# CPU-SOLDER_V2.net
KiCad netlist of a schematic drawn in EAGLE
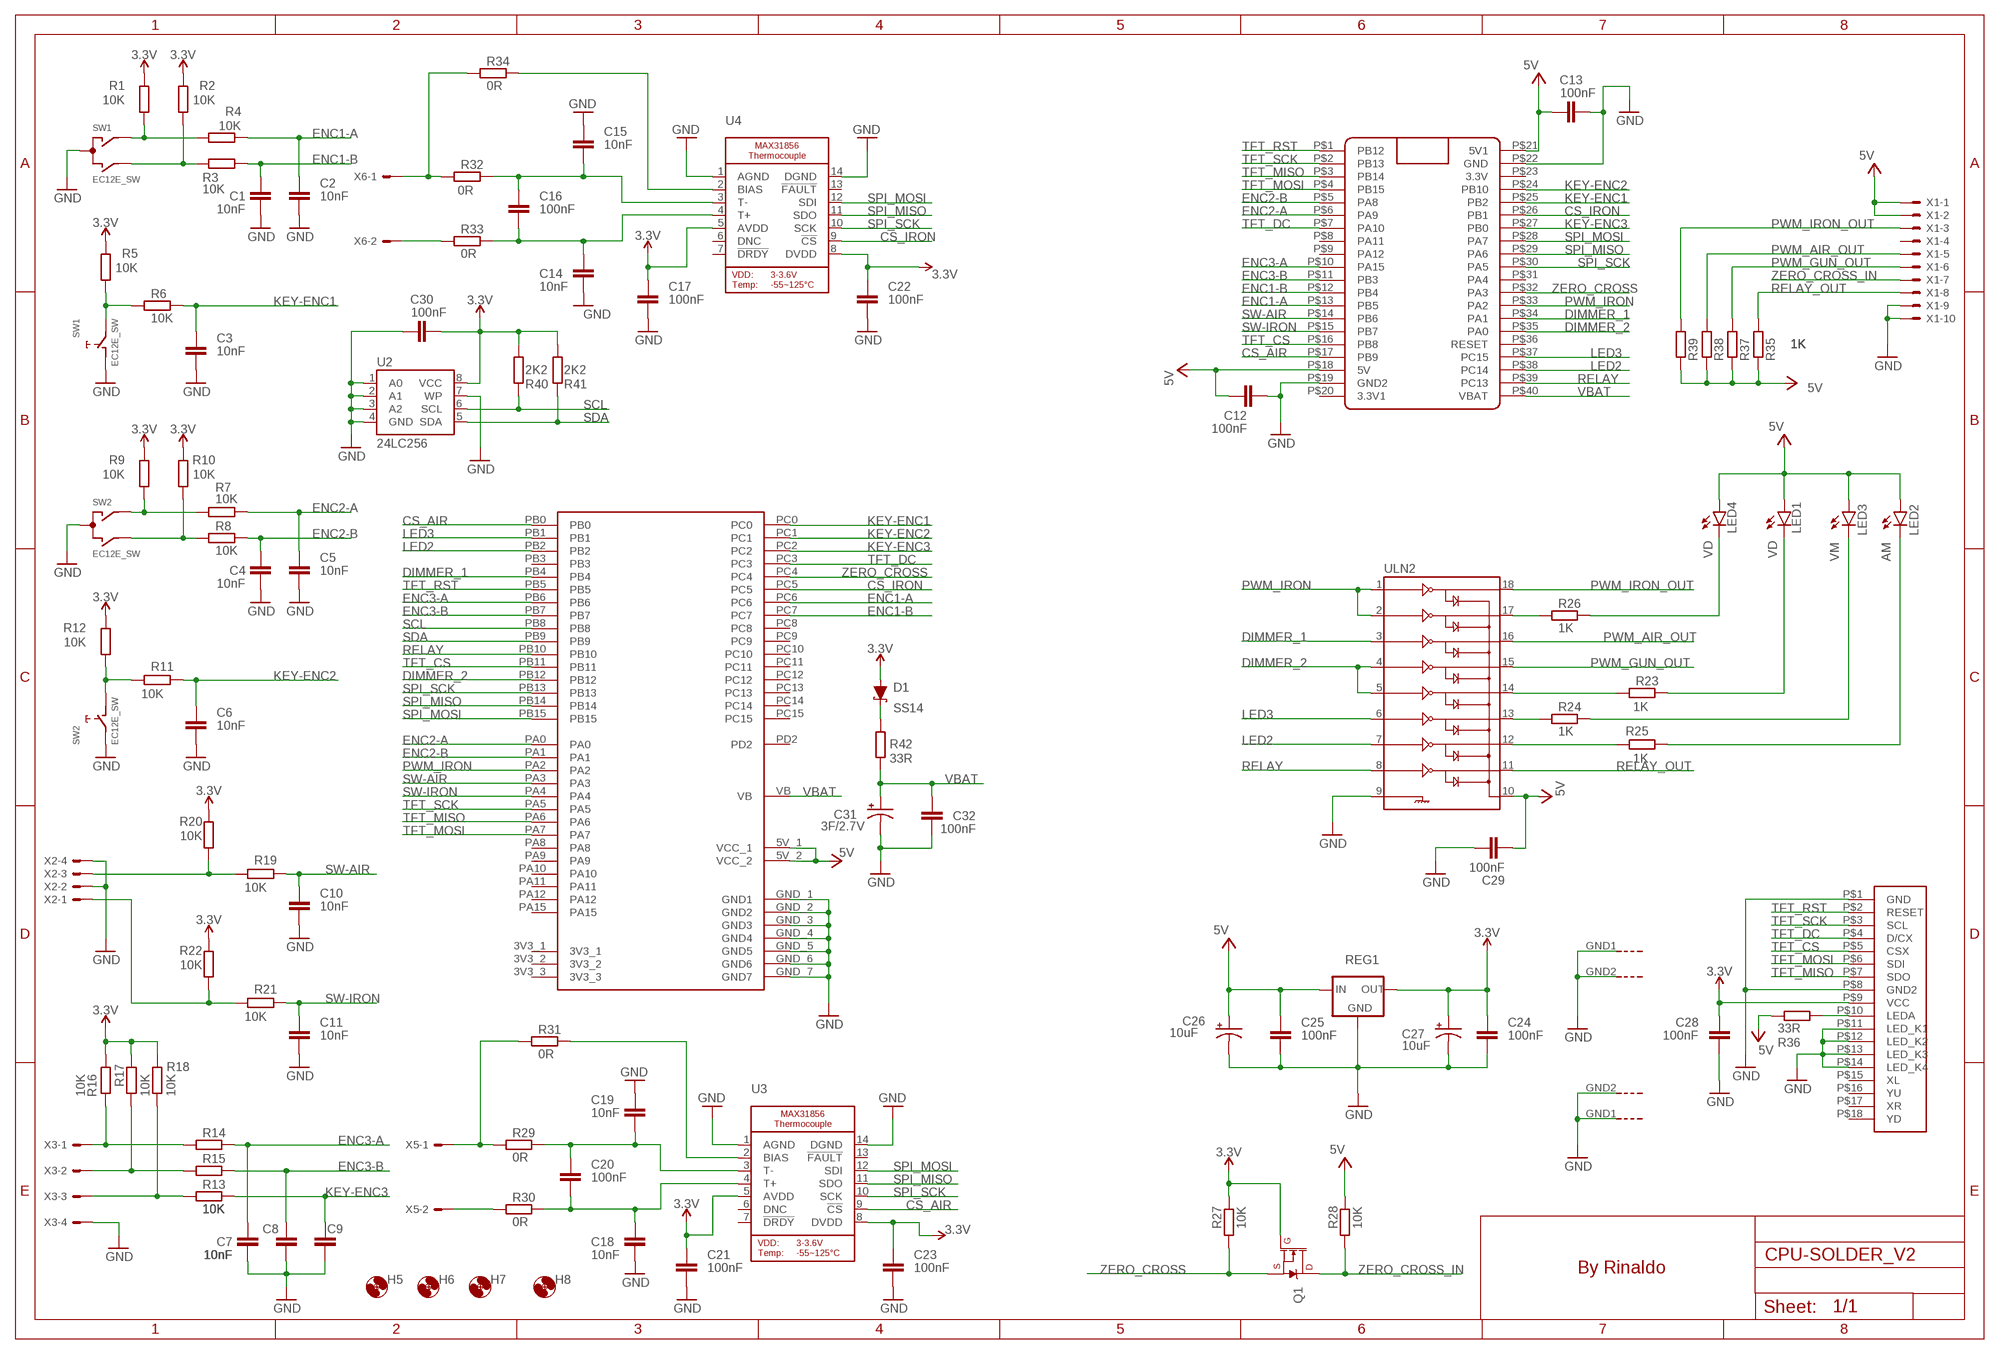
[diagram p0: schematic, sheet 1]

(export (version "E")
  (design (tool "Eeschema 10.0.6"))
  (components
    (comp (ref "C1")
      (value "10nF")
      (footprint "eagle-import:C0603")
      (libsource (lib "eagle-import") (part "C-EUC0603"))
    )
    (comp (ref "C2")
      (value "10nF")
      (footprint "eagle-import:C0603")
      (libsource (lib "eagle-import") (part "C-EUC0603"))
    )
    (comp (ref "C3")
      (value "10nF")
      (footprint "eagle-import:C0603")
      (libsource (lib "eagle-import") (part "C-EUC0603"))
    )
    (comp (ref "C4")
      (value "10nF")
      (footprint "eagle-import:C0603")
      (libsource (lib "eagle-import") (part "C-EUC0603"))
    )
    (comp (ref "C5")
      (value "10nF")
      (footprint "eagle-import:C0603")
      (libsource (lib "eagle-import") (part "C-EUC0603"))
    )
    (comp (ref "C6")
      (value "10nF")
      (footprint "eagle-import:C0603")
      (libsource (lib "eagle-import") (part "C-EUC0603"))
    )
    (comp (ref "C7")
      (value "10nF")
      (footprint "eagle-import:C0603")
      (libsource (lib "eagle-import") (part "C-EUC0603"))
    )
    (comp (ref "C8")
      (value "10nF")
      (footprint "eagle-import:C0603")
      (libsource (lib "eagle-import") (part "C-EUC0603"))
    )
    (comp (ref "C9")
      (value "10nF")
      (footprint "eagle-import:C0603")
      (libsource (lib "eagle-import") (part "C-EUC0603"))
    )
    (comp (ref "C10")
      (value "10nF")
      (footprint "eagle-import:C0603")
      (libsource (lib "eagle-import") (part "C-EUC0603"))
    )
    (comp (ref "C11")
      (value "10nF")
      (footprint "eagle-import:C0603")
      (libsource (lib "eagle-import") (part "C-EUC0603"))
    )
    (comp (ref "C12")
      (value "100nF")
      (footprint "eagle-import:C0603")
      (libsource (lib "eagle-import") (part "C-EUC0603"))
    )
    (comp (ref "C13")
      (value "100nF")
      (footprint "eagle-import:C0603")
      (libsource (lib "eagle-import") (part "C-EUC0603"))
    )
    (comp (ref "C14")
      (value "10nF")
      (footprint "eagle-import:C0603")
      (libsource (lib "eagle-import") (part "C-EUC0603"))
    )
    (comp (ref "C15")
      (value "10nF")
      (footprint "eagle-import:C0603")
      (libsource (lib "eagle-import") (part "C-EUC0603"))
    )
    (comp (ref "C16")
      (value "100nF")
      (footprint "eagle-import:C0603")
      (libsource (lib "eagle-import") (part "C-EUC0603"))
    )
    (comp (ref "C17")
      (value "100nF")
      (footprint "eagle-import:C0603")
      (libsource (lib "eagle-import") (part "C-EUC0603"))
    )
    (comp (ref "C18")
      (value "10nF")
      (footprint "eagle-import:C0603")
      (libsource (lib "eagle-import") (part "C-EUC0603"))
    )
    (comp (ref "C19")
      (value "10nF")
      (footprint "eagle-import:C0603")
      (libsource (lib "eagle-import") (part "C-EUC0603"))
    )
    (comp (ref "C20")
      (value "100nF")
      (footprint "eagle-import:C0603")
      (libsource (lib "eagle-import") (part "C-EUC0603"))
    )
    (comp (ref "C21")
      (value "100nF")
      (footprint "eagle-import:C0603")
      (libsource (lib "eagle-import") (part "C-EUC0603"))
    )
    (comp (ref "C22")
      (value "100nF")
      (footprint "eagle-import:C0603")
      (libsource (lib "eagle-import") (part "C-EUC0603"))
    )
    (comp (ref "C23")
      (value "100nF")
      (footprint "eagle-import:C0603")
      (libsource (lib "eagle-import") (part "C-EUC0603"))
    )
    (comp (ref "C24")
      (value "100nF")
      (footprint "eagle-import:C0603")
      (libsource (lib "eagle-import") (part "C-EUC0603"))
    )
    (comp (ref "C25")
      (value "100nF")
      (footprint "eagle-import:C0603")
      (libsource (lib "eagle-import") (part "C-EUC0603"))
    )
    (comp (ref "C26")
      (value "10uF")
      (footprint "eagle-import:EIA3528")
      (libsource (lib "eagle-import") (part "10UF-POLAR-EIA3528-20V-10%(TANT)"))
    )
    (comp (ref "C27")
      (value "10uF")
      (footprint "eagle-import:EIA3528")
      (libsource (lib "eagle-import") (part "10UF-POLAR-EIA3528-20V-10%(TANT)"))
    )
    (comp (ref "C28")
      (value "100nF")
      (footprint "eagle-import:C0603")
      (libsource (lib "eagle-import") (part "C-EUC0603"))
    )
    (comp (ref "C29")
      (value "100nF")
      (footprint "eagle-import:C0603")
      (libsource (lib "eagle-import") (part "C-EUC0603"))
    )
    (comp (ref "C30")
      (value "100nF")
      (footprint "eagle-import:C0603")
      (libsource (lib "eagle-import") (part "C-EUC0603"))
    )
    (comp (ref "C31")
      (value "3F/2.7V")
      (footprint "eagle-import:CPOL-RADIAL-1F-2.7V")
      (libsource (lib "eagle-import") (part "1F-2.7V(PTH)CPOL-RADIAL-1H-2.7V"))
    )
    (comp (ref "C32")
      (value "100nF")
      (footprint "eagle-import:C0603")
      (libsource (lib "eagle-import") (part "C-EUC0603"))
    )
    (comp (ref "D1")
      (value "SS14")
      (footprint "eagle-import:SMA-DIODE")
      (libsource (lib "eagle-import") (part "DIODE-SCHOTTKY-SS14"))
    )
    (comp (ref "H5")
      (value "MOUNT-HOLE3.6")
      (footprint "eagle-import:3,6")
      (libsource (lib "eagle-import") (part "MOUNT-HOLE3.6"))
    )
    (comp (ref "H6")
      (value "MOUNT-HOLE3.6")
      (footprint "eagle-import:3,6")
      (libsource (lib "eagle-import") (part "MOUNT-HOLE3.6"))
    )
    (comp (ref "H7")
      (value "MOUNT-HOLE3.6")
      (footprint "eagle-import:3,6")
      (libsource (lib "eagle-import") (part "MOUNT-HOLE3.6"))
    )
    (comp (ref "H8")
      (value "MOUNT-HOLE3.6")
      (footprint "eagle-import:3,6")
      (libsource (lib "eagle-import") (part "MOUNT-HOLE3.6"))
    )
    (comp (ref "LCD1")
      (value "ILI9341-3.2")
      (footprint "eagle-import:ILI9341-3.2")
      (libsource (lib "eagle-import") (part "ILI9341-3.2"))
    )
    (comp (ref "LED1")
      (value "VD")
      (footprint "eagle-import:LED5MM")
      (libsource (lib "eagle-import") (part "LED5MM"))
    )
    (comp (ref "LED2")
      (value "AM")
      (footprint "eagle-import:LED5MM")
      (libsource (lib "eagle-import") (part "LED5MM"))
    )
    (comp (ref "LED3")
      (value "VM")
      (footprint "eagle-import:LED5MM")
      (libsource (lib "eagle-import") (part "LED5MM"))
    )
    (comp (ref "LED4")
      (value "VD")
      (footprint "eagle-import:LED5MM")
      (libsource (lib "eagle-import") (part "LED5MM"))
    )
    (comp (ref "Q1")
      (value "220mA/50V/3.5Ω")
      (footprint "eagle-import:SOT23-3")
      (libsource (lib "eagle-import") (part "MOSFET-NCH-BSS138"))
    )
    (comp (ref "R1")
      (value "10K")
      (footprint "eagle-import:R0603")
      (libsource (lib "eagle-import") (part "R-EU_R0603"))
    )
    (comp (ref "R2")
      (value "10K")
      (footprint "eagle-import:R0603")
      (libsource (lib "eagle-import") (part "R-EU_R0603"))
    )
    (comp (ref "R3")
      (value "10K")
      (footprint "eagle-import:R0603")
      (libsource (lib "eagle-import") (part "R-EU_R0603"))
    )
    (comp (ref "R4")
      (value "10K")
      (footprint "eagle-import:R0603")
      (libsource (lib "eagle-import") (part "R-EU_R0603"))
    )
    (comp (ref "R5")
      (value "10K")
      (footprint "eagle-import:R0603")
      (libsource (lib "eagle-import") (part "R-EU_R0603"))
    )
    (comp (ref "R6")
      (value "10K")
      (footprint "eagle-import:R0603")
      (libsource (lib "eagle-import") (part "R-EU_R0603"))
    )
    (comp (ref "R7")
      (value "10K")
      (footprint "eagle-import:R0603")
      (libsource (lib "eagle-import") (part "R-EU_R0603"))
    )
    (comp (ref "R8")
      (value "10K")
      (footprint "eagle-import:R0603")
      (libsource (lib "eagle-import") (part "R-EU_R0603"))
    )
    (comp (ref "R9")
      (value "10K")
      (footprint "eagle-import:R0603")
      (libsource (lib "eagle-import") (part "R-EU_R0603"))
    )
    (comp (ref "R10")
      (value "10K")
      (footprint "eagle-import:R0603")
      (libsource (lib "eagle-import") (part "R-EU_R0603"))
    )
    (comp (ref "R11")
      (value "10K")
      (footprint "eagle-import:R0603")
      (libsource (lib "eagle-import") (part "R-EU_R0603"))
    )
    (comp (ref "R12")
      (value "10K")
      (footprint "eagle-import:R0603")
      (libsource (lib "eagle-import") (part "R-EU_R0603"))
    )
    (comp (ref "R13")
      (value "10K")
      (footprint "eagle-import:R0603")
      (libsource (lib "eagle-import") (part "R-EU_R0603"))
    )
    (comp (ref "R14")
      (value "10K")
      (footprint "eagle-import:R0603")
      (libsource (lib "eagle-import") (part "R-EU_R0603"))
    )
    (comp (ref "R15")
      (value "10K")
      (footprint "eagle-import:R0603")
      (libsource (lib "eagle-import") (part "R-EU_R0603"))
    )
    (comp (ref "R16")
      (value "10K")
      (footprint "eagle-import:R0603")
      (libsource (lib "eagle-import") (part "R-EU_R0603"))
    )
    (comp (ref "R17")
      (value "10K")
      (footprint "eagle-import:R0603")
      (libsource (lib "eagle-import") (part "R-EU_R0603"))
    )
    (comp (ref "R18")
      (value "10K")
      (footprint "eagle-import:R0603")
      (libsource (lib "eagle-import") (part "R-EU_R0603"))
    )
    (comp (ref "R19")
      (value "10K")
      (footprint "eagle-import:R0603")
      (libsource (lib "eagle-import") (part "R-EU_R0603"))
    )
    (comp (ref "R20")
      (value "10K")
      (footprint "eagle-import:R0603")
      (libsource (lib "eagle-import") (part "R-EU_R0603"))
    )
    (comp (ref "R21")
      (value "10K")
      (footprint "eagle-import:R0603")
      (libsource (lib "eagle-import") (part "R-EU_R0603"))
    )
    (comp (ref "R22")
      (value "10K")
      (footprint "eagle-import:R0603")
      (libsource (lib "eagle-import") (part "R-EU_R0603"))
    )
    (comp (ref "R23")
      (value "1K")
      (footprint "eagle-import:R0603")
      (libsource (lib "eagle-import") (part "R-EU_R0603"))
    )
    (comp (ref "R24")
      (value "1K")
      (footprint "eagle-import:R0603")
      (libsource (lib "eagle-import") (part "R-EU_R0603"))
    )
    (comp (ref "R25")
      (value "1K")
      (footprint "eagle-import:R0603")
      (libsource (lib "eagle-import") (part "R-EU_R0603"))
    )
    (comp (ref "R26")
      (value "1K")
      (footprint "eagle-import:R0603")
      (libsource (lib "eagle-import") (part "R-EU_R0603"))
    )
    (comp (ref "R27")
      (value "10K")
      (footprint "eagle-import:R0603")
      (libsource (lib "eagle-import") (part "R-EU_R0603"))
    )
    (comp (ref "R28")
      (value "10K")
      (footprint "eagle-import:R0603")
      (libsource (lib "eagle-import") (part "R-EU_R0603"))
    )
    (comp (ref "R29")
      (value "0R")
      (footprint "eagle-import:R0603")
      (libsource (lib "eagle-import") (part "R-EU_R0603"))
    )
    (comp (ref "R30")
      (value "0R")
      (footprint "eagle-import:R0603")
      (libsource (lib "eagle-import") (part "R-EU_R0603"))
    )
    (comp (ref "R31")
      (value "0R")
      (footprint "eagle-import:R0603")
      (libsource (lib "eagle-import") (part "R-EU_R0603"))
    )
    (comp (ref "R32")
      (value "0R")
      (footprint "eagle-import:R0603")
      (libsource (lib "eagle-import") (part "R-EU_R0603"))
    )
    (comp (ref "R33")
      (value "0R")
      (footprint "eagle-import:R0603")
      (libsource (lib "eagle-import") (part "R-EU_R0603"))
    )
    (comp (ref "R34")
      (value "0R")
      (footprint "eagle-import:R0603")
      (libsource (lib "eagle-import") (part "R-EU_R0603"))
    )
    (comp (ref "R35")
      (value "1K")
      (footprint "eagle-import:R0603")
      (libsource (lib "eagle-import") (part "R-EU_R0603"))
    )
    (comp (ref "R36")
      (value "33R")
      (footprint "eagle-import:R2512")
      (libsource (lib "eagle-import") (part "R-EU_R2512"))
    )
    (comp (ref "R37")
      (value "1K")
      (footprint "eagle-import:R0603")
      (libsource (lib "eagle-import") (part "R-EU_R0603"))
    )
    (comp (ref "R38")
      (value "1K")
      (footprint "eagle-import:R0603")
      (libsource (lib "eagle-import") (part "R-EU_R0603"))
    )
    (comp (ref "R39")
      (value "1K")
      (footprint "eagle-import:R0603")
      (libsource (lib "eagle-import") (part "R-EU_R0603"))
    )
    (comp (ref "R40")
      (value "2K2")
      (footprint "eagle-import:R0603")
      (libsource (lib "eagle-import") (part "R-EU_R0603"))
    )
    (comp (ref "R41")
      (value "2K2")
      (footprint "eagle-import:R0603")
      (libsource (lib "eagle-import") (part "R-EU_R0603"))
    )
    (comp (ref "R42")
      (value "33R")
      (footprint "eagle-import:R2512")
      (libsource (lib "eagle-import") (part "R-EU_R2512"))
    )
    (comp (ref "REG1")
      (value "V_REG_LD1117VXXLD1117-SMD")
      (footprint "eagle-import:SOT223")
      (libsource (lib "eagle-import") (part "V_REG_LD1117VXXLD1117-SMD"))
    )
    (comp (ref "SW1")
      (value "EC12E_SW")
      (footprint "eagle-import:ALPS_EC12E_SW")
      (fields (field (name "MPN") "EC12E2424407"))
      (libsource (lib "eagle-import") (part "EC12E_SW"))
    )
    (comp (ref "SW2")
      (value "EC12E_SW")
      (footprint "eagle-import:ALPS_EC12E_SW")
      (fields (field (name "MPN") "EC12E2424407"))
      (libsource (lib "eagle-import") (part "EC12E_SW"))
    )
    (comp (ref "U1")
      (value "STM32-F411")
      (footprint "eagle-import:BLACK-PILL-STM32_BLUE_PILL")
      (libsource (lib "eagle-import") (part "BLACK-PILL-STM32_BLACK_PILL"))
    )
    (comp (ref "U2")
      (value "24LC256")
      (footprint "eagle-import:SO08")
      (libsource (lib "eagle-import") (part "EEPROM-I2C256K"))
    )
    (comp (ref "U3")
      (value "MICROBUILDER_MAX31856")
      (footprint "eagle-import:MICROBUILDER_TSSOP14")
      (libsource (lib "eagle-import") (part "MICROBUILDER_MAX31856"))
    )
    (comp (ref "U4")
      (value "MICROBUILDER_MAX31856")
      (footprint "eagle-import:MICROBUILDER_TSSOP14")
      (libsource (lib "eagle-import") (part "MICROBUILDER_MAX31856"))
    )
    (comp (ref "U5")
      (value "F405_WEACT")
      (footprint "eagle-import:F405_WEACT")
      (libsource (lib "eagle-import") (part "F405_WEACT"))
    )
    (comp (ref "ULN2")
      (value "ULN2803SOICW")
      (footprint "eagle-import:SO18L")
      (libsource (lib "eagle-import") (part "ULN2803SOICW"))
    )
    (comp (ref "X1")
      (value "JST-XH-10-PIN-ROUND-PAD")
      (footprint "eagle-import:JST-XH-10-PACKAGE-ROUND-PAD")
      (libsource (lib "eagle-import") (part "JST-XH-10-PIN-ROUND-PAD"))
    )
    (comp (ref "X2")
      (value "JST-XH-04-PIN-ROUND-PAD")
      (footprint "eagle-import:JST-XH-04-PACKAGE-ROUND-PAD")
      (libsource (lib "eagle-import") (part "JST-XH-04-PIN-ROUND-PAD"))
    )
    (comp (ref "X3")
      (value "JST-XH-04-PIN-ROUND-PAD")
      (footprint "eagle-import:JST-XH-04-PACKAGE-ROUND-PAD")
      (libsource (lib "eagle-import") (part "JST-XH-04-PIN-ROUND-PAD"))
    )
    (comp (ref "X5")
      (value "JST-XH-02-PIN-ROUND-PAD")
      (footprint "eagle-import:JST-XH-02-PACKAGE-ROUND-PAD")
      (libsource (lib "eagle-import") (part "JST-XH-02-PIN-ROUND-PAD"))
    )
    (comp (ref "X6")
      (value "JST-XH-02-PIN-ROUND-PAD")
      (footprint "eagle-import:JST-XH-02-PACKAGE-ROUND-PAD")
      (libsource (lib "eagle-import") (part "JST-XH-02-PIN-ROUND-PAD"))
    )
  )
  (nets
    (net (code "1") (name "/CS_AIR") (class "Default")
      (node (ref "U1") (pin "P$17") (pinfunction "PB9_P$17") (pintype "bidirectional"))
      (node (ref "U3") (pin "9") (pinfunction "~{CS}_9") (pintype "input"))
      (node (ref "U5") (pin "PB0") (pinfunction "PB0_PB0") (pintype "bidirectional"))
    )
    (net (code "2") (name "/CS_IRON") (class "Default")
      (node (ref "U1") (pin "P$26") (pinfunction "PB1_P$26") (pintype "bidirectional"))
      (node (ref "U4") (pin "9") (pinfunction "~{CS}_9") (pintype "input"))
      (node (ref "U5") (pin "PC5") (pinfunction "PC5_PC5") (pintype "bidirectional"))
    )
    (net (code "3") (name "/DIMMER_1") (class "Default")
      (node (ref "U1") (pin "P$34") (pinfunction "PA1_P$34") (pintype "bidirectional"))
      (node (ref "U5") (pin "PB4") (pinfunction "PB4_PB4") (pintype "bidirectional"))
      (node (ref "ULN2") (pin "3") (pinfunction "3_3") (pintype "bidirectional"))
    )
    (net (code "4") (name "/DIMMER_2") (class "Default")
      (node (ref "U1") (pin "P$35") (pinfunction "PA0_P$35") (pintype "bidirectional"))
      (node (ref "U5") (pin "PB12") (pinfunction "PB12_PB12") (pintype "bidirectional"))
      (node (ref "ULN2") (pin "4") (pinfunction "4_4") (pintype "bidirectional"))
      (node (ref "ULN2") (pin "5") (pinfunction "5_5") (pintype "bidirectional"))
    )
    (net (code "5") (name "/ENC1-A") (class "Default")
      (node (ref "C2") (pin "1") (pinfunction "1_1") (pintype "passive"))
      (node (ref "R3") (pin "1") (pinfunction "1_1") (pintype "passive"))
      (node (ref "U1") (pin "P$13") (pinfunction "PB5_P$13") (pintype "bidirectional"))
      (node (ref "U5") (pin "PC6") (pinfunction "PC6_PC6") (pintype "bidirectional"))
    )
    (net (code "6") (name "/ENC1-B") (class "Default")
      (node (ref "C1") (pin "1") (pinfunction "1_1") (pintype "passive"))
      (node (ref "R4") (pin "2") (pinfunction "2_2") (pintype "passive"))
      (node (ref "U1") (pin "P$12") (pinfunction "PB4_P$12") (pintype "bidirectional"))
      (node (ref "U5") (pin "PC7") (pinfunction "PC7_PC7") (pintype "bidirectional"))
    )
    (net (code "7") (name "/ENC2-A") (class "Default")
      (node (ref "C5") (pin "1") (pinfunction "1_1") (pintype "passive"))
      (node (ref "R7") (pin "2") (pinfunction "2_2") (pintype "passive"))
      (node (ref "U1") (pin "P$6") (pinfunction "PA9_P$6") (pintype "bidirectional"))
      (node (ref "U5") (pin "PA0") (pinfunction "PA0_PA0") (pintype "bidirectional"))
    )
    (net (code "8") (name "/ENC2-B") (class "Default")
      (node (ref "C4") (pin "1") (pinfunction "1_1") (pintype "passive"))
      (node (ref "R8") (pin "2") (pinfunction "2_2") (pintype "passive"))
      (node (ref "U1") (pin "P$5") (pinfunction "PA8_P$5") (pintype "bidirectional"))
      (node (ref "U5") (pin "PA1") (pinfunction "PA1_PA1") (pintype "bidirectional"))
    )
    (net (code "9") (name "/ENC3-A") (class "Default")
      (node (ref "C7") (pin "1") (pinfunction "1_1") (pintype "passive"))
      (node (ref "R14") (pin "2") (pinfunction "2_2") (pintype "passive"))
      (node (ref "U1") (pin "P$10") (pinfunction "PA15_P$10") (pintype "bidirectional"))
      (node (ref "U5") (pin "PB6") (pinfunction "PB6_PB6") (pintype "bidirectional"))
    )
    (net (code "10") (name "/ENC3-B") (class "Default")
      (node (ref "C8") (pin "1") (pinfunction "1_1") (pintype "passive"))
      (node (ref "R15") (pin "2") (pinfunction "2_2") (pintype "passive"))
      (node (ref "U1") (pin "P$11") (pinfunction "PB3_P$11") (pintype "bidirectional"))
      (node (ref "U5") (pin "PB7") (pinfunction "PB7_PB7") (pintype "bidirectional"))
    )
    (net (code "11") (name "/KEY-ENC1") (class "Default")
      (node (ref "C3") (pin "1") (pinfunction "1_1") (pintype "passive"))
      (node (ref "R6") (pin "1") (pinfunction "1_1") (pintype "passive"))
      (node (ref "U1") (pin "P$25") (pinfunction "PB2_P$25") (pintype "bidirectional"))
      (node (ref "U5") (pin "PC0") (pinfunction "PC0_PC0") (pintype "bidirectional"))
    )
    (net (code "12") (name "/KEY-ENC2") (class "Default")
      (node (ref "C6") (pin "1") (pinfunction "1_1") (pintype "passive"))
      (node (ref "R11") (pin "1") (pinfunction "1_1") (pintype "passive"))
      (node (ref "U1") (pin "P$24") (pinfunction "PB10_P$24") (pintype "bidirectional"))
      (node (ref "U5") (pin "PC1") (pinfunction "PC1_PC1") (pintype "bidirectional"))
    )
    (net (code "13") (name "/KEY-ENC3") (class "Default")
      (node (ref "C9") (pin "1") (pinfunction "1_1") (pintype "passive"))
      (node (ref "R13") (pin "2") (pinfunction "2_2") (pintype "passive"))
      (node (ref "U1") (pin "P$27") (pinfunction "PB0_P$27") (pintype "bidirectional"))
      (node (ref "U5") (pin "PC2") (pinfunction "PC2_PC2") (pintype "bidirectional"))
    )
    (net (code "14") (name "/LED2") (class "Default")
      (node (ref "U1") (pin "P$38") (pinfunction "PC14_P$38") (pintype "bidirectional"))
      (node (ref "U5") (pin "PB2") (pinfunction "PB2_PB2") (pintype "bidirectional"))
      (node (ref "ULN2") (pin "7") (pinfunction "7_7") (pintype "bidirectional"))
    )
    (net (code "15") (name "/LED3") (class "Default")
      (node (ref "U1") (pin "P$37") (pinfunction "PC15_P$37") (pintype "bidirectional"))
      (node (ref "U5") (pin "PB1") (pinfunction "PB1_PB1") (pintype "bidirectional"))
      (node (ref "ULN2") (pin "6") (pinfunction "6_6") (pintype "bidirectional"))
    )
    (net (code "16") (name "/PWM_AIR_OUT") (class "Default")
      (node (ref "R38") (pin "1") (pinfunction "1_1") (pintype "passive"))
      (node (ref "ULN2") (pin "16") (pinfunction "16_16") (pintype "bidirectional"))
      (node (ref "X1") (pin "5") (pinfunction "S_5") (pintype "passive"))
    )
    (net (code "17") (name "/PWM_GUN_OUT") (class "Default")
      (node (ref "R37") (pin "1") (pinfunction "1_1") (pintype "passive"))
      (node (ref "ULN2") (pin "15") (pinfunction "15_15") (pintype "bidirectional"))
      (node (ref "X1") (pin "6") (pinfunction "S_6") (pintype "passive"))
    )
    (net (code "18") (name "/PWM_IRON") (class "Default")
      (node (ref "U1") (pin "P$33") (pinfunction "PA2_P$33") (pintype "bidirectional"))
      (node (ref "U5") (pin "PA2") (pinfunction "PA2_PA2") (pintype "bidirectional"))
      (node (ref "ULN2") (pin "1") (pinfunction "1_1") (pintype "bidirectional"))
      (node (ref "ULN2") (pin "2") (pinfunction "2_2") (pintype "bidirectional"))
    )
    (net (code "19") (name "/PWM_IRON_OUT") (class "Default")
      (node (ref "R39") (pin "1") (pinfunction "1_1") (pintype "passive"))
      (node (ref "ULN2") (pin "18") (pinfunction "18_18") (pintype "bidirectional"))
      (node (ref "X1") (pin "3") (pinfunction "S_3") (pintype "passive"))
    )
    (net (code "20") (name "/RELAY") (class "Default")
      (node (ref "U1") (pin "P$39") (pinfunction "PC13_P$39") (pintype "bidirectional"))
      (node (ref "U5") (pin "PB10") (pinfunction "PB10_PB10") (pintype "bidirectional"))
      (node (ref "ULN2") (pin "8") (pinfunction "8_8") (pintype "bidirectional"))
    )
    (net (code "21") (name "/RELAY_OUT") (class "Default")
      (node (ref "R35") (pin "1") (pinfunction "1_1") (pintype "passive"))
      (node (ref "ULN2") (pin "11") (pinfunction "11_11") (pintype "bidirectional"))
      (node (ref "X1") (pin "8") (pinfunction "S_8") (pintype "passive"))
    )
    (net (code "22") (name "/SCL") (class "Default")
      (node (ref "R40") (pin "2") (pinfunction "2_2") (pintype "passive"))
      (node (ref "U2") (pin "6") (pinfunction "SCL_6") (pintype "bidirectional"))
      (node (ref "U5") (pin "PB8") (pinfunction "PB8_PB8") (pintype "bidirectional"))
    )
    (net (code "23") (name "/SDA") (class "Default")
      (node (ref "R41") (pin "2") (pinfunction "2_2") (pintype "passive"))
      (node (ref "U2") (pin "5") (pinfunction "SDA_5") (pintype "bidirectional"))
      (node (ref "U5") (pin "PB9") (pinfunction "PB9_PB9") (pintype "bidirectional"))
    )
    (net (code "24") (name "/SPI_MISO") (class "Default")
      (node (ref "U1") (pin "P$29") (pinfunction "PA6_P$29") (pintype "bidirectional"))
      (node (ref "U3") (pin "11") (pinfunction "SDO_11") (pintype "output"))
      (node (ref "U4") (pin "11") (pinfunction "SDO_11") (pintype "output"))
      (node (ref "U5") (pin "PB14") (pinfunction "PB14_PB14") (pintype "bidirectional"))
    )
    (net (code "25") (name "/SPI_MOSI") (class "Default")
      (node (ref "U1") (pin "P$28") (pinfunction "PA7_P$28") (pintype "bidirectional"))
      (node (ref "U3") (pin "12") (pinfunction "SDI_12") (pintype "input"))
      (node (ref "U4") (pin "12") (pinfunction "SDI_12") (pintype "input"))
      (node (ref "U5") (pin "PB15") (pinfunction "PB15_PB15") (pintype "bidirectional"))
    )
    (net (code "26") (name "/SPI_SCK") (class "Default")
      (node (ref "U1") (pin "P$30") (pinfunction "PA5_P$30") (pintype "bidirectional"))
      (node (ref "U3") (pin "10") (pinfunction "SCK_10") (pintype "input"))
      (node (ref "U4") (pin "10") (pinfunction "SCK_10") (pintype "input"))
      (node (ref "U5") (pin "PB13") (pinfunction "PB13_PB13") (pintype "bidirectional"))
    )
    (net (code "27") (name "/SW-AIR") (class "Default")
      (node (ref "C10") (pin "1") (pinfunction "1_1") (pintype "passive"))
      (node (ref "R19") (pin "1") (pinfunction "1_1") (pintype "passive"))
      (node (ref "U1") (pin "P$14") (pinfunction "PB6_P$14") (pintype "bidirectional"))
      (node (ref "U5") (pin "PA3") (pinfunction "PA3_PA3") (pintype "bidirectional"))
    )
    (net (code "28") (name "/SW-IRON") (class "Default")
      (node (ref "C11") (pin "1") (pinfunction "1_1") (pintype "passive"))
      (node (ref "R21") (pin "1") (pinfunction "1_1") (pintype "passive"))
      (node (ref "U1") (pin "P$15") (pinfunction "PB7_P$15") (pintype "bidirectional"))
      (node (ref "U5") (pin "PA4") (pinfunction "PA4_PA4") (pintype "bidirectional"))
    )
    (net (code "29") (name "/TFT_CS") (class "Default")
      (node (ref "LCD1") (pin "P$5") (pinfunction "CSX_P$5") (pintype "bidirectional"))
      (node (ref "U1") (pin "P$16") (pinfunction "PB8_P$16") (pintype "bidirectional"))
      (node (ref "U5") (pin "PB11") (pinfunction "PB11_PB11") (pintype "bidirectional"))
    )
    (net (code "30") (name "/TFT_DC") (class "Default")
      (node (ref "LCD1") (pin "P$4") (pinfunction "D/CX_P$4") (pintype "bidirectional"))
      (node (ref "U1") (pin "P$7") (pinfunction "PA10_P$7") (pintype "bidirectional"))
      (node (ref "U5") (pin "PC3") (pinfunction "PC3_PC3") (pintype "bidirectional"))
    )
    (net (code "31") (name "/TFT_MISO") (class "Default")
      (node (ref "LCD1") (pin "P$7") (pinfunction "SDO_P$7") (pintype "bidirectional"))
      (node (ref "U1") (pin "P$3") (pinfunction "PB14_P$3") (pintype "bidirectional"))
      (node (ref "U5") (pin "PA6") (pinfunction "PA6_PA6") (pintype "bidirectional"))
    )
    (net (code "32") (name "/TFT_MOSI") (class "Default")
      (node (ref "LCD1") (pin "P$6") (pinfunction "SDI_P$6") (pintype "bidirectional"))
      (node (ref "U1") (pin "P$4") (pinfunction "PB15_P$4") (pintype "bidirectional"))
      (node (ref "U5") (pin "PA7") (pinfunction "PA7_PA7") (pintype "bidirectional"))
    )
    (net (code "33") (name "/TFT_RST") (class "Default")
      (node (ref "LCD1") (pin "P$2") (pinfunction "RESET_P$2") (pintype "bidirectional"))
      (node (ref "U1") (pin "P$1") (pinfunction "PB12_P$1") (pintype "bidirectional"))
      (node (ref "U5") (pin "PB5") (pinfunction "PB5_PB5") (pintype "bidirectional"))
    )
    (net (code "34") (name "/TFT_SCK") (class "Default")
      (node (ref "LCD1") (pin "P$3") (pinfunction "SCL_P$3") (pintype "bidirectional"))
      (node (ref "U1") (pin "P$2") (pinfunction "PB13_P$2") (pintype "bidirectional"))
      (node (ref "U5") (pin "PA5") (pinfunction "PA5_PA5") (pintype "bidirectional"))
    )
    (net (code "35") (name "/VBAT") (class "Default")
      (node (ref "C31") (pin "+") (pinfunction "+_+") (pintype "passive"))
      (node (ref "C32") (pin "1") (pinfunction "1_1") (pintype "passive"))
      (node (ref "R42") (pin "1") (pinfunction "1_1") (pintype "passive"))
      (node (ref "U1") (pin "P$40") (pinfunction "VBAT_P$40") (pintype "bidirectional"))
      (node (ref "U5") (pin "VB") (pinfunction "VB_VB") (pintype "bidirectional"))
    )
    (net (code "36") (name "/ZERO_CROSS") (class "Default")
      (node (ref "Q1") (pin "2") (pinfunction "S_2") (pintype "bidirectional"))
      (node (ref "R27") (pin "1") (pinfunction "1_1") (pintype "passive"))
      (node (ref "U1") (pin "P$32") (pinfunction "PA3_P$32") (pintype "bidirectional"))
      (node (ref "U5") (pin "PC4") (pinfunction "PC4_PC4") (pintype "bidirectional"))
    )
    (net (code "37") (name "/ZERO_CROSS_IN") (class "Default")
      (node (ref "Q1") (pin "3") (pinfunction "D_3") (pintype "bidirectional"))
      (node (ref "R28") (pin "1") (pinfunction "1_1") (pintype "passive"))
      (node (ref "X1") (pin "7") (pinfunction "S_7") (pintype "passive"))
    )
    (net (code "38") (name "3.3V") (class "Default")
      (node (ref "C17") (pin "2") (pinfunction "2_2") (pintype "passive"))
      (node (ref "C21") (pin "2") (pinfunction "2_2") (pintype "passive"))
      (node (ref "C22") (pin "2") (pinfunction "2_2") (pintype "passive"))
      (node (ref "C23") (pin "2") (pinfunction "2_2") (pintype "passive"))
      (node (ref "C24") (pin "2") (pinfunction "2_2") (pintype "passive"))
      (node (ref "C27") (pin "A") (pinfunction "+_A") (pintype "passive"))
      (node (ref "C28") (pin "2") (pinfunction "2_2") (pintype "passive"))
      (node (ref "C30") (pin "1") (pinfunction "1_1") (pintype "passive"))
      (node (ref "D1") (pin "A") (pinfunction "A_A") (pintype "passive"))
      (node (ref "LCD1") (pin "P$9") (pinfunction "VCC_P$9") (pintype "bidirectional"))
      (node (ref "Q1") (pin "1") (pinfunction "G_1") (pintype "bidirectional"))
      (node (ref "R1") (pin "2") (pinfunction "2_2") (pintype "passive"))
      (node (ref "R10") (pin "2") (pinfunction "2_2") (pintype "passive"))
      (node (ref "R12") (pin "2") (pinfunction "2_2") (pintype "passive"))
      (node (ref "R16") (pin "2") (pinfunction "2_2") (pintype "passive"))
      (node (ref "R17") (pin "2") (pinfunction "2_2") (pintype "passive"))
      (node (ref "R18") (pin "2") (pinfunction "2_2") (pintype "passive"))
      (node (ref "R2") (pin "2") (pinfunction "2_2") (pintype "passive"))
      (node (ref "R20") (pin "2") (pinfunction "2_2") (pintype "passive"))
      (node (ref "R22") (pin "2") (pinfunction "2_2") (pintype "passive"))
      (node (ref "R27") (pin "2") (pinfunction "2_2") (pintype "passive"))
      (node (ref "R40") (pin "1") (pinfunction "1_1") (pintype "passive"))
      (node (ref "R41") (pin "1") (pinfunction "1_1") (pintype "passive"))
      (node (ref "R5") (pin "2") (pinfunction "2_2") (pintype "passive"))
      (node (ref "R9") (pin "2") (pinfunction "2_2") (pintype "passive"))
      (node (ref "REG1") (pin "2") (pinfunction "OUT_2") (pintype "passive"))
      (node (ref "U2") (pin "8") (pinfunction "VCC_8") (pintype "power_in"))
      (node (ref "U3") (pin "5") (pinfunction "AVDD_5") (pintype "power_in"))
      (node (ref "U3") (pin "8") (pinfunction "DVDD_8") (pintype "power_in"))
      (node (ref "U4") (pin "5") (pinfunction "AVDD_5") (pintype "power_in"))
      (node (ref "U4") (pin "8") (pinfunction "DVDD_8") (pintype "power_in"))
    )
    (net (code "39") (name "5V") (class "Default")
      (node (ref "C12") (pin "1") (pinfunction "1_1") (pintype "passive"))
      (node (ref "C13") (pin "1") (pinfunction "1_1") (pintype "passive"))
      (node (ref "C25") (pin "2") (pinfunction "2_2") (pintype "passive"))
      (node (ref "C26") (pin "A") (pinfunction "+_A") (pintype "passive"))
      (node (ref "C29") (pin "1") (pinfunction "1_1") (pintype "passive"))
      (node (ref "LED1") (pin "A") (pinfunction "A_A") (pintype "passive"))
      (node (ref "LED2") (pin "A") (pinfunction "A_A") (pintype "passive"))
      (node (ref "LED3") (pin "A") (pinfunction "A_A") (pintype "passive"))
      (node (ref "LED4") (pin "A") (pinfunction "A_A") (pintype "passive"))
      (node (ref "R28") (pin "2") (pinfunction "2_2") (pintype "passive"))
      (node (ref "R35") (pin "2") (pinfunction "2_2") (pintype "passive"))
      (node (ref "R36") (pin "1") (pinfunction "1_1") (pintype "passive"))
      (node (ref "R37") (pin "2") (pinfunction "2_2") (pintype "passive"))
      (node (ref "R38") (pin "2") (pinfunction "2_2") (pintype "passive"))
      (node (ref "R39") (pin "2") (pinfunction "2_2") (pintype "passive"))
      (node (ref "REG1") (pin "3") (pinfunction "IN_3") (pintype "input"))
      (node (ref "U1") (pin "P$18") (pinfunction "5V_P$18") (pintype "bidirectional"))
      (node (ref "U1") (pin "P$21") (pinfunction "5V1_P$21") (pintype "power_in"))
      (node (ref "U5") (pin "5V_1") (pinfunction "VCC_1_5V_1") (pintype "bidirectional"))
      (node (ref "U5") (pin "5V_2") (pinfunction "VCC_2_5V_2") (pintype "bidirectional"))
      (node (ref "ULN2") (pin "10") (pinfunction "10_10") (pintype "bidirectional"))
      (node (ref "X1") (pin "1") (pinfunction "S_1") (pintype "passive"))
      (node (ref "X1") (pin "2") (pinfunction "S_2") (pintype "passive"))
    )
    (net (code "40") (name "GND") (class "Default")
      (node (ref "C1") (pin "2") (pinfunction "2_2") (pintype "passive"))
      (node (ref "C10") (pin "2") (pinfunction "2_2") (pintype "passive"))
      (node (ref "C11") (pin "2") (pinfunction "2_2") (pintype "passive"))
      (node (ref "C12") (pin "2") (pinfunction "2_2") (pintype "passive"))
      (node (ref "C13") (pin "2") (pinfunction "2_2") (pintype "passive"))
      (node (ref "C14") (pin "1") (pinfunction "1_1") (pintype "passive"))
      (node (ref "C15") (pin "2") (pinfunction "2_2") (pintype "passive"))
      (node (ref "C17") (pin "1") (pinfunction "1_1") (pintype "passive"))
      (node (ref "C18") (pin "1") (pinfunction "1_1") (pintype "passive"))
      (node (ref "C19") (pin "2") (pinfunction "2_2") (pintype "passive"))
      (node (ref "C2") (pin "2") (pinfunction "2_2") (pintype "passive"))
      (node (ref "C21") (pin "1") (pinfunction "1_1") (pintype "passive"))
      (node (ref "C22") (pin "1") (pinfunction "1_1") (pintype "passive"))
      (node (ref "C23") (pin "1") (pinfunction "1_1") (pintype "passive"))
      (node (ref "C24") (pin "1") (pinfunction "1_1") (pintype "passive"))
      (node (ref "C25") (pin "1") (pinfunction "1_1") (pintype "passive"))
      (node (ref "C26") (pin "C") (pinfunction "-_C") (pintype "passive"))
      (node (ref "C27") (pin "C") (pinfunction "-_C") (pintype "passive"))
      (node (ref "C28") (pin "1") (pinfunction "1_1") (pintype "passive"))
      (node (ref "C29") (pin "2") (pinfunction "2_2") (pintype "passive"))
      (node (ref "C3") (pin "2") (pinfunction "2_2") (pintype "passive"))
      (node (ref "C30") (pin "2") (pinfunction "2_2") (pintype "passive"))
      (node (ref "C31") (pin "-") (pinfunction "-_-") (pintype "passive"))
      (node (ref "C32") (pin "2") (pinfunction "2_2") (pintype "passive"))
      (node (ref "C4") (pin "2") (pinfunction "2_2") (pintype "passive"))
      (node (ref "C5") (pin "2") (pinfunction "2_2") (pintype "passive"))
      (node (ref "C6") (pin "2") (pinfunction "2_2") (pintype "passive"))
      (node (ref "C7") (pin "2") (pinfunction "2_2") (pintype "passive"))
      (node (ref "C8") (pin "2") (pinfunction "2_2") (pintype "passive"))
      (node (ref "C9") (pin "2") (pinfunction "2_2") (pintype "passive"))
      (node (ref "LCD1") (pin "P$1") (pinfunction "GND_P$1") (pintype "bidirectional"))
      (node (ref "LCD1") (pin "P$11") (pinfunction "LED_K1_P$11") (pintype "bidirectional"))
      (node (ref "LCD1") (pin "P$12") (pinfunction "LED_K2_P$12") (pintype "bidirectional"))
      (node (ref "LCD1") (pin "P$13") (pinfunction "LED_K3_P$13") (pintype "bidirectional"))
      (node (ref "LCD1") (pin "P$14") (pinfunction "LED_K4_P$14") (pintype "bidirectional"))
      (node (ref "LCD1") (pin "P$8") (pinfunction "GND2_P$8") (pintype "bidirectional"))
      (node (ref "REG1") (pin "1") (pinfunction "GND_1") (pintype "input"))
      (node (ref "SW1") (pin "C") (pinfunction "C_C") (pintype "passive"))
      (node (ref "SW1") (pin "D") (pinfunction "1_D") (pintype "passive"))
      (node (ref "SW1") (pin "GND1") (pinfunction "G_GND1") (pintype "passive"))
      (node (ref "SW1") (pin "GND2") (pinfunction "G_GND2") (pintype "passive"))
      (node (ref "SW2") (pin "C") (pinfunction "C_C") (pintype "passive"))
      (node (ref "SW2") (pin "E") (pinfunction "2_E") (pintype "passive"))
      (node (ref "SW2") (pin "GND1") (pinfunction "G_GND1") (pintype "passive"))
      (node (ref "SW2") (pin "GND2") (pinfunction "G_GND2") (pintype "passive"))
      (node (ref "U1") (pin "P$19") (pinfunction "GND2_P$19") (pintype "bidirectional"))
      (node (ref "U1") (pin "P$22") (pinfunction "GND_P$22") (pintype "bidirectional"))
      (node (ref "U2") (pin "1") (pinfunction "A0_1") (pintype "bidirectional"))
      (node (ref "U2") (pin "2") (pinfunction "A1_2") (pintype "bidirectional"))
      (node (ref "U2") (pin "3") (pinfunction "A2_3") (pintype "bidirectional"))
      (node (ref "U2") (pin "4") (pinfunction "GND_4") (pintype "power_in"))
      (node (ref "U2") (pin "7") (pinfunction "WP_7") (pintype "bidirectional"))
      (node (ref "U3") (pin "1") (pinfunction "AGND_1") (pintype "power_in"))
      (node (ref "U3") (pin "14") (pinfunction "DGND_14") (pintype "power_in"))
      (node (ref "U4") (pin "1") (pinfunction "AGND_1") (pintype "power_in"))
      (node (ref "U4") (pin "14") (pinfunction "DGND_14") (pintype "power_in"))
      (node (ref "U5") (pin "GND_1") (pinfunction "GND1_GND_1") (pintype "bidirectional"))
      (node (ref "U5") (pin "GND_2") (pinfunction "GND2_GND_2") (pintype "bidirectional"))
      (node (ref "U5") (pin "GND_3") (pinfunction "GND3_GND_3") (pintype "bidirectional"))
      (node (ref "U5") (pin "GND_4") (pinfunction "GND4_GND_4") (pintype "bidirectional"))
      (node (ref "U5") (pin "GND_5") (pinfunction "GND5_GND_5") (pintype "bidirectional"))
      (node (ref "U5") (pin "GND_6") (pinfunction "GND6_GND_6") (pintype "bidirectional"))
      (node (ref "U5") (pin "GND_7") (pinfunction "GND7_GND_7") (pintype "bidirectional"))
      (node (ref "ULN2") (pin "9") (pinfunction "9_9") (pintype "bidirectional"))
      (node (ref "X1") (pin "10") (pinfunction "S_10") (pintype "passive"))
      (node (ref "X1") (pin "9") (pinfunction "S_9") (pintype "passive"))
      (node (ref "X2") (pin "2") (pinfunction "S_2") (pintype "passive"))
      (node (ref "X2") (pin "4") (pinfunction "S_4") (pintype "passive"))
      (node (ref "X3") (pin "4") (pinfunction "S_4") (pintype "passive"))
    )
    (net (code "41") (name "Net-(D1-PadC)") (class "Default")
      (node (ref "D1") (pin "C") (pinfunction "C_C") (pintype "passive"))
      (node (ref "R42") (pin "2") (pinfunction "2_2") (pintype "passive"))
    )
    (net (code "42") (name "Net-(LCD1-LEDA)") (class "Default")
      (node (ref "LCD1") (pin "P$10") (pinfunction "LEDA_P$10") (pintype "bidirectional"))
      (node (ref "R36") (pin "2") (pinfunction "2_2") (pintype "passive"))
    )
    (net (code "43") (name "Net-(LED1-C)") (class "Default")
      (node (ref "LED1") (pin "K") (pinfunction "C_K") (pintype "passive"))
      (node (ref "R23") (pin "1") (pinfunction "1_1") (pintype "passive"))
    )
    (net (code "44") (name "Net-(LED2-C)") (class "Default")
      (node (ref "LED2") (pin "K") (pinfunction "C_K") (pintype "passive"))
      (node (ref "R25") (pin "2") (pinfunction "2_2") (pintype "passive"))
    )
    (net (code "45") (name "Net-(LED3-C)") (class "Default")
      (node (ref "LED3") (pin "K") (pinfunction "C_K") (pintype "passive"))
      (node (ref "R24") (pin "1") (pinfunction "1_1") (pintype "passive"))
    )
    (net (code "46") (name "Net-(LED4-C)") (class "Default")
      (node (ref "LED4") (pin "K") (pinfunction "C_K") (pintype "passive"))
      (node (ref "R26") (pin "2") (pinfunction "2_2") (pintype "passive"))
    )
    (net (code "47") (name "Net-(R1-Pad1)") (class "Default")
      (node (ref "R1") (pin "1") (pinfunction "1_1") (pintype "passive"))
      (node (ref "R3") (pin "2") (pinfunction "2_2") (pintype "passive"))
      (node (ref "SW1") (pin "A") (pinfunction "A_A") (pintype "passive"))
    )
    (net (code "48") (name "Net-(R2-Pad1)") (class "Default")
      (node (ref "R2") (pin "1") (pinfunction "1_1") (pintype "passive"))
      (node (ref "R4") (pin "1") (pinfunction "1_1") (pintype "passive"))
      (node (ref "SW1") (pin "B") (pinfunction "B_B") (pintype "passive"))
    )
    (net (code "49") (name "Net-(R7-Pad1)") (class "Default")
      (node (ref "R7") (pin "1") (pinfunction "1_1") (pintype "passive"))
      (node (ref "R9") (pin "1") (pinfunction "1_1") (pintype "passive"))
      (node (ref "SW2") (pin "A") (pinfunction "A_A") (pintype "passive"))
    )
    (net (code "50") (name "Net-(R10-Pad1)") (class "Default")
      (node (ref "R10") (pin "1") (pinfunction "1_1") (pintype "passive"))
      (node (ref "R8") (pin "1") (pinfunction "1_1") (pintype "passive"))
      (node (ref "SW2") (pin "B") (pinfunction "B_B") (pintype "passive"))
    )
    (net (code "51") (name "Net-(R23-Pad2)") (class "Default")
      (node (ref "R23") (pin "2") (pinfunction "2_2") (pintype "passive"))
      (node (ref "ULN2") (pin "14") (pinfunction "14_14") (pintype "bidirectional"))
    )
    (net (code "52") (name "Net-(R24-Pad2)") (class "Default")
      (node (ref "R24") (pin "2") (pinfunction "2_2") (pintype "passive"))
      (node (ref "ULN2") (pin "13") (pinfunction "13_13") (pintype "bidirectional"))
    )
    (net (code "53") (name "Net-(R25-Pad1)") (class "Default")
      (node (ref "R25") (pin "1") (pinfunction "1_1") (pintype "passive"))
      (node (ref "ULN2") (pin "12") (pinfunction "12_12") (pintype "bidirectional"))
    )
    (net (code "54") (name "Net-(R26-Pad1)") (class "Default")
      (node (ref "R26") (pin "1") (pinfunction "1_1") (pintype "passive"))
      (node (ref "ULN2") (pin "17") (pinfunction "17_17") (pintype "bidirectional"))
    )
    (net (code "55") (name "Net-(SW1B-2)") (class "Default")
      (node (ref "R5") (pin "1") (pinfunction "1_1") (pintype "passive"))
      (node (ref "R6") (pin "2") (pinfunction "2_2") (pintype "passive"))
      (node (ref "SW1") (pin "E") (pinfunction "2_E") (pintype "passive"))
    )
    (net (code "56") (name "Net-(SW2B-1)") (class "Default")
      (node (ref "R11") (pin "2") (pinfunction "2_2") (pintype "passive"))
      (node (ref "R12") (pin "1") (pinfunction "1_1") (pintype "passive"))
      (node (ref "SW2") (pin "D") (pinfunction "1_D") (pintype "passive"))
    )
    (net (code "57") (name "Net-(U3-BIAS)") (class "Default")
      (node (ref "R31") (pin "1") (pinfunction "1_1") (pintype "passive"))
      (node (ref "U3") (pin "2") (pinfunction "BIAS_2") (pintype "power_in"))
    )
    (net (code "58") (name "Net-(U3-T+)") (class "Default")
      (node (ref "C18") (pin "2") (pinfunction "2_2") (pintype "passive"))
      (node (ref "C20") (pin "1") (pinfunction "1_1") (pintype "passive"))
      (node (ref "R30") (pin "1") (pinfunction "1_1") (pintype "passive"))
      (node (ref "U3") (pin "4") (pinfunction "T+_4") (pintype "input"))
    )
    (net (code "59") (name "Net-(U3-T-)") (class "Default")
      (node (ref "C19") (pin "1") (pinfunction "1_1") (pintype "passive"))
      (node (ref "C20") (pin "2") (pinfunction "2_2") (pintype "passive"))
      (node (ref "R29") (pin "1") (pinfunction "1_1") (pintype "passive"))
      (node (ref "U3") (pin "3") (pinfunction "T-_3") (pintype "input"))
    )
    (net (code "60") (name "Net-(U4-BIAS)") (class "Default")
      (node (ref "R34") (pin "1") (pinfunction "1_1") (pintype "passive"))
      (node (ref "U4") (pin "2") (pinfunction "BIAS_2") (pintype "power_in"))
    )
    (net (code "61") (name "Net-(U4-T+)") (class "Default")
      (node (ref "C14") (pin "2") (pinfunction "2_2") (pintype "passive"))
      (node (ref "C16") (pin "1") (pinfunction "1_1") (pintype "passive"))
      (node (ref "R33") (pin "1") (pinfunction "1_1") (pintype "passive"))
      (node (ref "U4") (pin "4") (pinfunction "T+_4") (pintype "input"))
    )
    (net (code "62") (name "Net-(U4-T-)") (class "Default")
      (node (ref "C15") (pin "1") (pinfunction "1_1") (pintype "passive"))
      (node (ref "C16") (pin "2") (pinfunction "2_2") (pintype "passive"))
      (node (ref "R32") (pin "1") (pinfunction "1_1") (pintype "passive"))
      (node (ref "U4") (pin "3") (pinfunction "T-_3") (pintype "input"))
    )
    (net (code "63") (name "Net-(X2A-S)") (class "Default")
      (node (ref "R21") (pin "2") (pinfunction "2_2") (pintype "passive"))
      (node (ref "R22") (pin "1") (pinfunction "1_1") (pintype "passive"))
      (node (ref "X2") (pin "1") (pinfunction "S_1") (pintype "passive"))
    )
    (net (code "64") (name "Net-(X2C-S)") (class "Default")
      (node (ref "R19") (pin "2") (pinfunction "2_2") (pintype "passive"))
      (node (ref "R20") (pin "1") (pinfunction "1_1") (pintype "passive"))
      (node (ref "X2") (pin "3") (pinfunction "S_3") (pintype "passive"))
    )
    (net (code "65") (name "Net-(X3A-S)") (class "Default")
      (node (ref "R14") (pin "1") (pinfunction "1_1") (pintype "passive"))
      (node (ref "R16") (pin "1") (pinfunction "1_1") (pintype "passive"))
      (node (ref "X3") (pin "1") (pinfunction "S_1") (pintype "passive"))
    )
    (net (code "66") (name "Net-(X3B-S)") (class "Default")
      (node (ref "R15") (pin "1") (pinfunction "1_1") (pintype "passive"))
      (node (ref "R17") (pin "1") (pinfunction "1_1") (pintype "passive"))
      (node (ref "X3") (pin "2") (pinfunction "S_2") (pintype "passive"))
    )
    (net (code "67") (name "Net-(X3C-S)") (class "Default")
      (node (ref "R13") (pin "1") (pinfunction "1_1") (pintype "passive"))
      (node (ref "R18") (pin "1") (pinfunction "1_1") (pintype "passive"))
      (node (ref "X3") (pin "3") (pinfunction "S_3") (pintype "passive"))
    )
    (net (code "68") (name "Net-(X5A-S)") (class "Default")
      (node (ref "R29") (pin "2") (pinfunction "2_2") (pintype "passive"))
      (node (ref "R31") (pin "2") (pinfunction "2_2") (pintype "passive"))
      (node (ref "X5") (pin "1") (pinfunction "S_1") (pintype "passive"))
    )
    (net (code "69") (name "Net-(X5B-S)") (class "Default")
      (node (ref "R30") (pin "2") (pinfunction "2_2") (pintype "passive"))
      (node (ref "X5") (pin "2") (pinfunction "S_2") (pintype "passive"))
    )
    (net (code "70") (name "Net-(X6A-S)") (class "Default")
      (node (ref "R32") (pin "2") (pinfunction "2_2") (pintype "passive"))
      (node (ref "R34") (pin "2") (pinfunction "2_2") (pintype "passive"))
      (node (ref "X6") (pin "1") (pinfunction "S_1") (pintype "passive"))
    )
    (net (code "71") (name "Net-(X6B-S)") (class "Default")
      (node (ref "R33") (pin "2") (pinfunction "2_2") (pintype "passive"))
      (node (ref "X6") (pin "2") (pinfunction "S_2") (pintype "passive"))
    )
    (net (code "72") (name "unconnected-(LCD1-XL-PadP$15)") (class "Default")
      (node (ref "LCD1") (pin "P$15") (pinfunction "XL_P$15") (pintype "bidirectional"))
    )
    (net (code "73") (name "unconnected-(LCD1-XR-PadP$17)") (class "Default")
      (node (ref "LCD1") (pin "P$17") (pinfunction "XR_P$17") (pintype "bidirectional"))
    )
    (net (code "74") (name "unconnected-(LCD1-YD-PadP$18)") (class "Default")
      (node (ref "LCD1") (pin "P$18") (pinfunction "YD_P$18") (pintype "bidirectional"))
    )
    (net (code "75") (name "unconnected-(LCD1-YU-PadP$16)") (class "Default")
      (node (ref "LCD1") (pin "P$16") (pinfunction "YU_P$16") (pintype "bidirectional"))
    )
    (net (code "76") (name "unconnected-(U1-3.3V-PadP$23)") (class "Default")
      (node (ref "U1") (pin "P$23") (pinfunction "3.3V_P$23") (pintype "bidirectional"))
    )
    (net (code "77") (name "unconnected-(U1-3.3V1-PadP$20)") (class "Default")
      (node (ref "U1") (pin "P$20") (pinfunction "3.3V1_P$20") (pintype "bidirectional"))
    )
    (net (code "78") (name "unconnected-(U1-PA4-PadP$31)") (class "Default")
      (node (ref "U1") (pin "P$31") (pinfunction "PA4_P$31") (pintype "bidirectional"))
    )
    (net (code "79") (name "unconnected-(U1-PA11-PadP$8)") (class "Default")
      (node (ref "U1") (pin "P$8") (pinfunction "PA11_P$8") (pintype "bidirectional"))
    )
    (net (code "80") (name "unconnected-(U1-PA12-PadP$9)") (class "Default")
      (node (ref "U1") (pin "P$9") (pinfunction "PA12_P$9") (pintype "bidirectional"))
    )
    (net (code "81") (name "unconnected-(U1-RESET-PadP$36)") (class "Default")
      (node (ref "U1") (pin "P$36") (pinfunction "RESET_P$36") (pintype "bidirectional"))
    )
    (net (code "82") (name "unconnected-(U3-DNC-Pad6)") (class "Default")
      (node (ref "U3") (pin "6") (pinfunction "DNC_6") (pintype "no_connect"))
    )
    (net (code "83") (name "unconnected-(U3-~{DRDY}-Pad7)") (class "Default")
      (node (ref "U3") (pin "7") (pinfunction "~{DRDY}_7") (pintype "output"))
    )
    (net (code "84") (name "unconnected-(U3-~{FAULT}-Pad13)") (class "Default")
      (node (ref "U3") (pin "13") (pinfunction "~{FAULT}_13") (pintype "output"))
    )
    (net (code "85") (name "unconnected-(U4-DNC-Pad6)") (class "Default")
      (node (ref "U4") (pin "6") (pinfunction "DNC_6") (pintype "no_connect"))
    )
    (net (code "86") (name "unconnected-(U4-~{DRDY}-Pad7)") (class "Default")
      (node (ref "U4") (pin "7") (pinfunction "~{DRDY}_7") (pintype "output"))
    )
    (net (code "87") (name "unconnected-(U4-~{FAULT}-Pad13)") (class "Default")
      (node (ref "U4") (pin "13") (pinfunction "~{FAULT}_13") (pintype "output"))
    )
    (net (code "88") (name "unconnected-(U5-Pad3V3_1)") (class "Default")
      (node (ref "U5") (pin "3V3_1") (pinfunction "3V3_1_3V3_1") (pintype "bidirectional"))
    )
    (net (code "89") (name "unconnected-(U5-Pad3V3_2)") (class "Default")
      (node (ref "U5") (pin "3V3_2") (pinfunction "3V3_2_3V3_2") (pintype "bidirectional"))
    )
    (net (code "90") (name "unconnected-(U5-Pad3V3_3)") (class "Default")
      (node (ref "U5") (pin "3V3_3") (pinfunction "3V3_3_3V3_3") (pintype "bidirectional"))
    )
    (net (code "91") (name "unconnected-(U5-PadPA8)") (class "Default")
      (node (ref "U5") (pin "PA8") (pinfunction "PA8_PA8") (pintype "bidirectional"))
    )
    (net (code "92") (name "unconnected-(U5-PadPA9)") (class "Default")
      (node (ref "U5") (pin "PA9") (pinfunction "PA9_PA9") (pintype "bidirectional"))
    )
    (net (code "93") (name "unconnected-(U5-PadPA10)") (class "Default")
      (node (ref "U5") (pin "PA10") (pinfunction "PA10_PA10") (pintype "bidirectional"))
    )
    (net (code "94") (name "unconnected-(U5-PadPA11)") (class "Default")
      (node (ref "U5") (pin "PA11") (pinfunction "PA11_PA11") (pintype "bidirectional"))
    )
    (net (code "95") (name "unconnected-(U5-PadPA12)") (class "Default")
      (node (ref "U5") (pin "PA12") (pinfunction "PA12_PA12") (pintype "bidirectional"))
    )
    (net (code "96") (name "unconnected-(U5-PadPA15)") (class "Default")
      (node (ref "U5") (pin "PA15") (pinfunction "PA15_PA15") (pintype "bidirectional"))
    )
    (net (code "97") (name "unconnected-(U5-PadPB3)") (class "Default")
      (node (ref "U5") (pin "PB3") (pinfunction "PB3_PB3") (pintype "bidirectional"))
    )
    (net (code "98") (name "unconnected-(U5-PadPC8)") (class "Default")
      (node (ref "U5") (pin "PC8") (pinfunction "PC8_PC8") (pintype "bidirectional"))
    )
    (net (code "99") (name "unconnected-(U5-PadPC9)") (class "Default")
      (node (ref "U5") (pin "PC9") (pinfunction "PC9_PC9") (pintype "bidirectional"))
    )
    (net (code "100") (name "unconnected-(U5-PadPC10)") (class "Default")
      (node (ref "U5") (pin "PC10") (pinfunction "PC10_PC10") (pintype "bidirectional"))
    )
    (net (code "101") (name "unconnected-(U5-PadPC11)") (class "Default")
      (node (ref "U5") (pin "PC11") (pinfunction "PC11_PC11") (pintype "bidirectional"))
    )
    (net (code "102") (name "unconnected-(U5-PadPC12)") (class "Default")
      (node (ref "U5") (pin "PC12") (pinfunction "PC12_PC12") (pintype "bidirectional"))
    )
    (net (code "103") (name "unconnected-(U5-PadPC13)") (class "Default")
      (node (ref "U5") (pin "PC13") (pinfunction "PC13_PC13") (pintype "bidirectional"))
    )
    (net (code "104") (name "unconnected-(U5-PadPC14)") (class "Default")
      (node (ref "U5") (pin "PC14") (pinfunction "PC14_PC14") (pintype "bidirectional"))
    )
    (net (code "105") (name "unconnected-(U5-PadPC15)") (class "Default")
      (node (ref "U5") (pin "PC15") (pinfunction "PC15_PC15") (pintype "bidirectional"))
    )
    (net (code "106") (name "unconnected-(U5-PadPD2)") (class "Default")
      (node (ref "U5") (pin "PD2") (pinfunction "PD2_PD2") (pintype "bidirectional"))
    )
    (net (code "107") (name "unconnected-(X1E-S-Pad4)") (class "Default")
      (node (ref "X1") (pin "4") (pinfunction "S_4") (pintype "passive"))
    )
  )
)
